# SMPS.net
KiCad netlist of a schematic drawn in Altium Designer
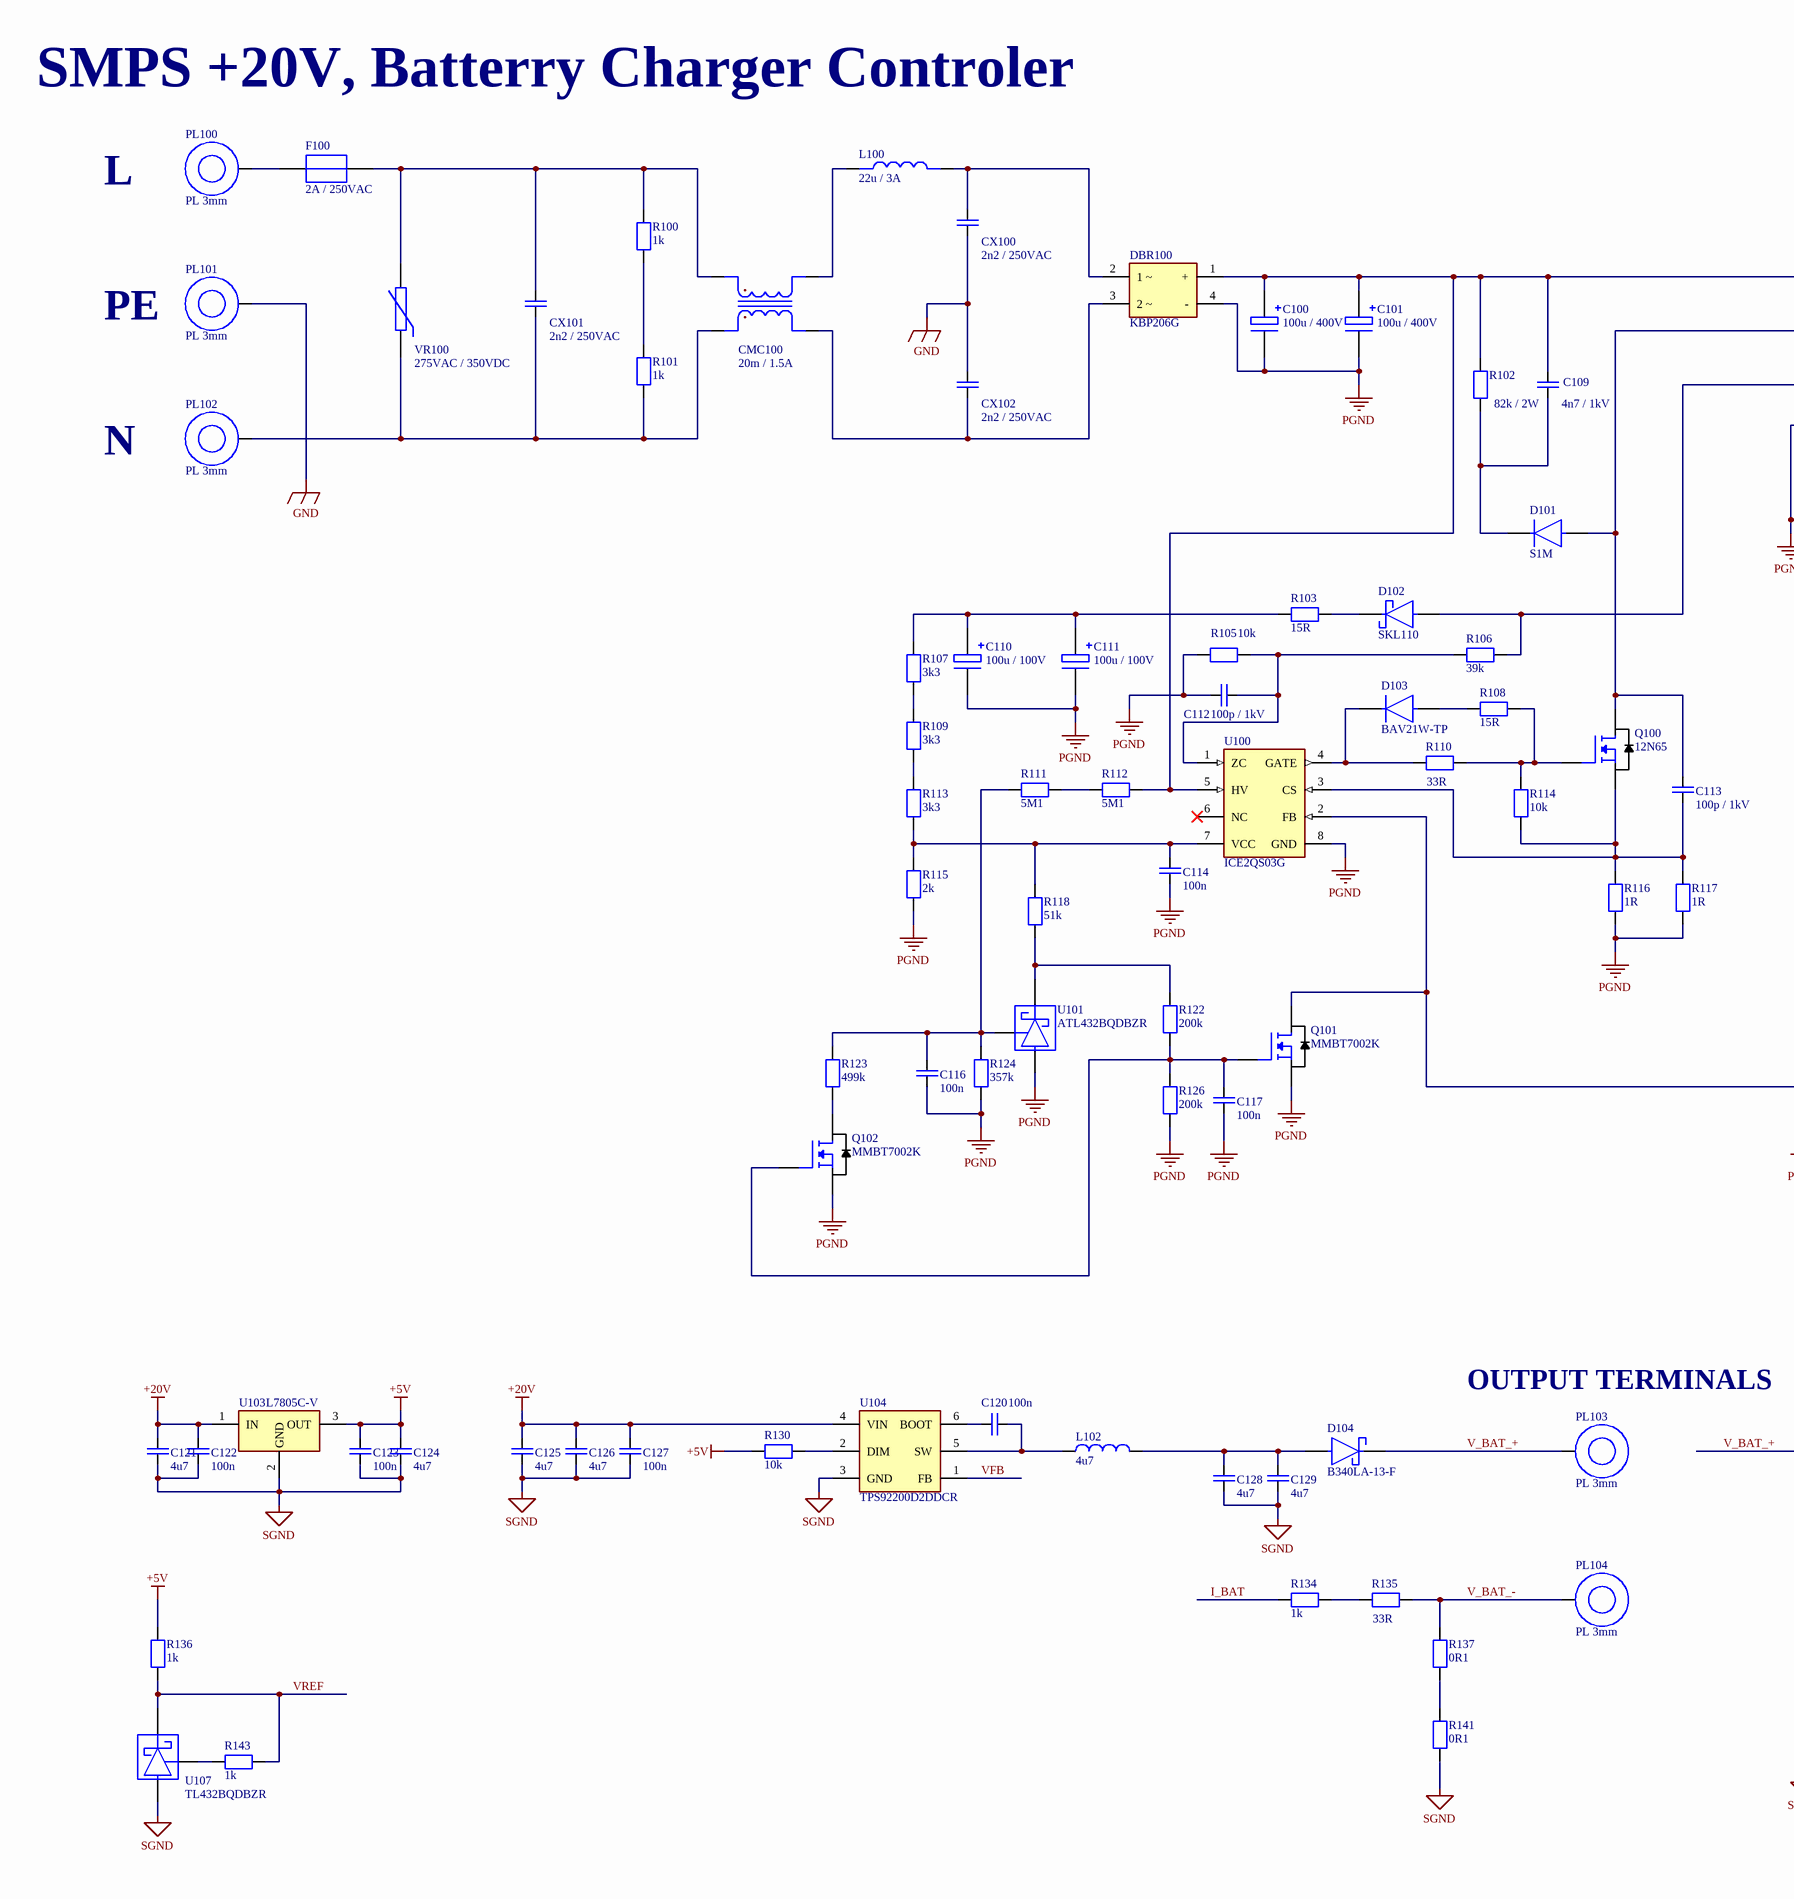
[diagram p0: SMPS.SchDoc, left]
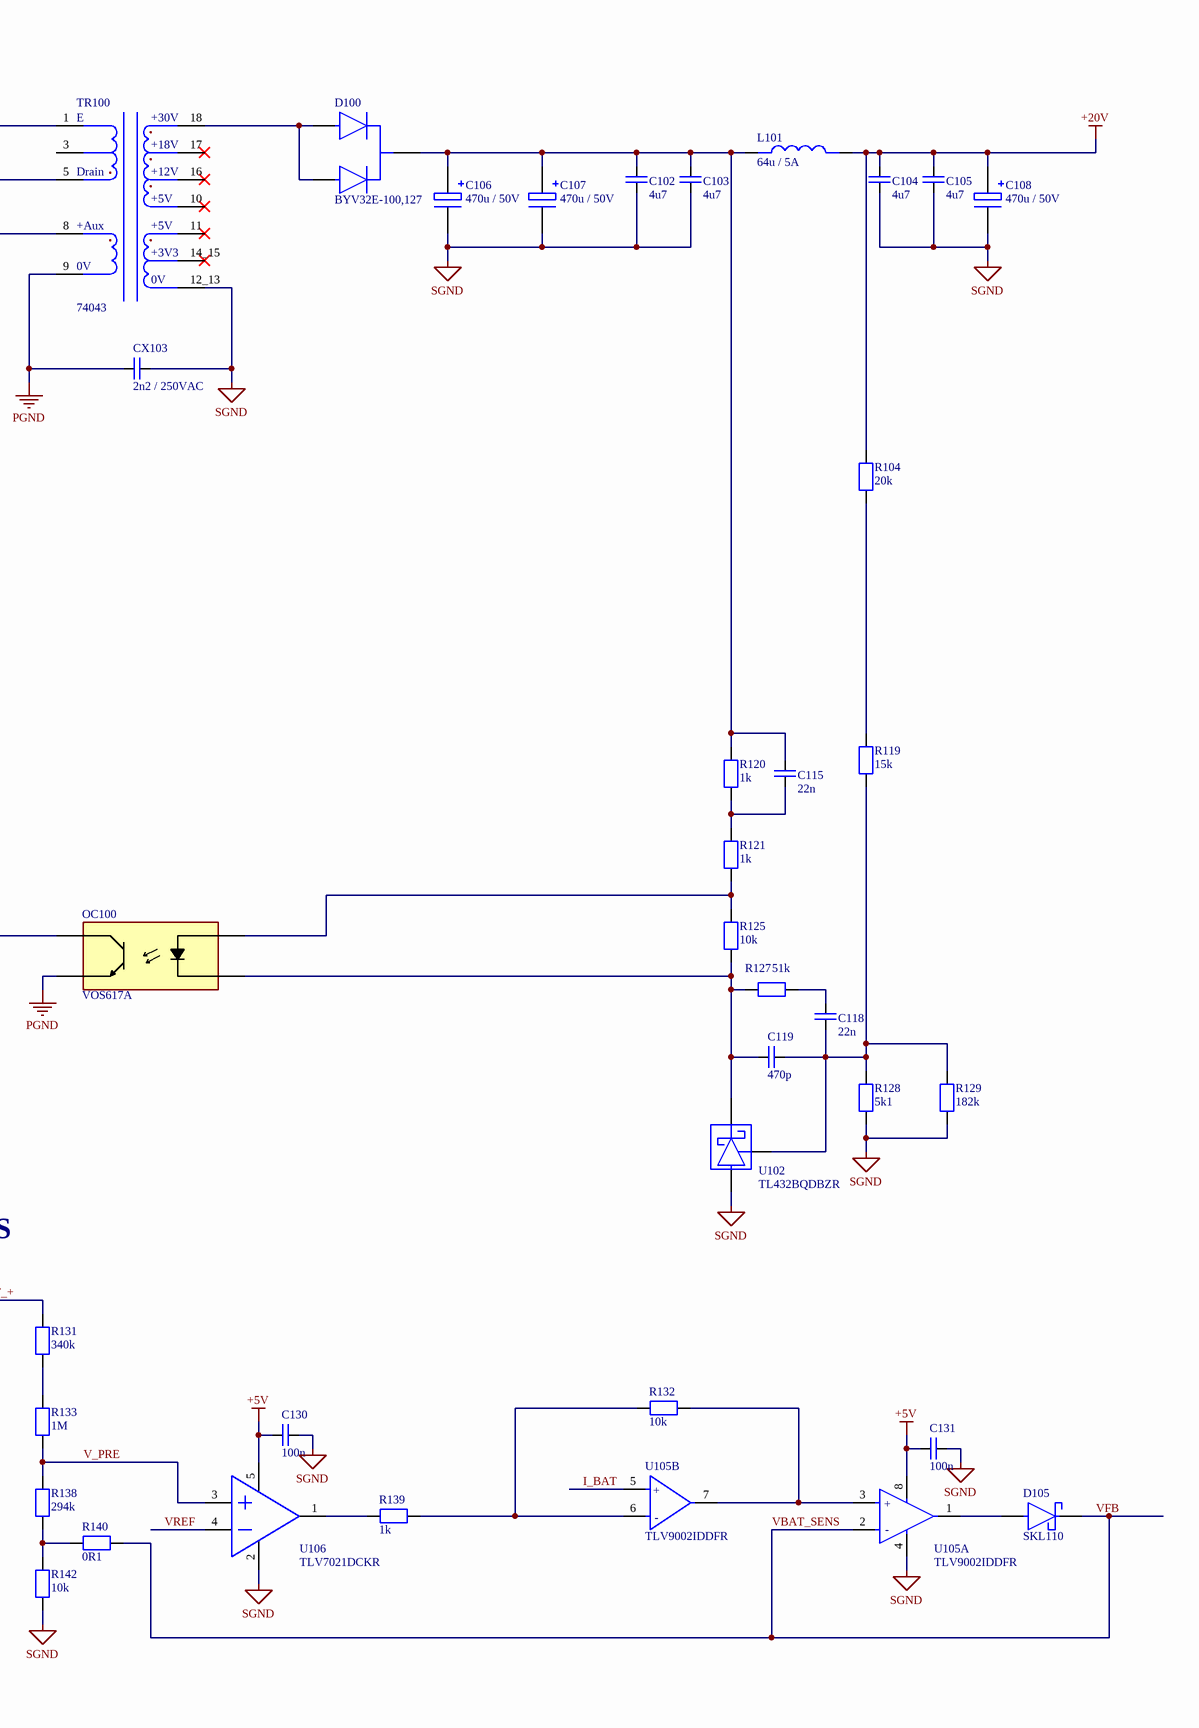
[diagram p1: SMPS.SchDoc, right]

(export (version "E")
  (design (tool "Eeschema 10.0.6"))
  (components
    (comp (ref "C100")
      (value "100u / 400V")
      (footprint "EL_CAP_16X7_5")
      (description "Cap Aluminum Lytic 100uF 400V 20% (16 X 35.5mm) Radial 7.5mm 850mA 12000h 105C Automotive Bulk")
      (fields
        (field (name "MANUFACTURER") "Nichicon")
        (field (name "MANUFACTURER PART NUMBER") "UCY2G101MHD")
      )
      (libsource (lib "ER_SCHEMATIC_LIBRARY") (part "UCY2G101MHD"))
    )
    (comp (ref "C101")
      (value "100u / 400V")
      (footprint "EL_CAP_16X7_5")
      (description "Cap Aluminum Lytic 100uF 400V 20% (16 X 35.5mm) Radial 7.5mm 850mA 12000h 105C Automotive Bulk")
      (fields
        (field (name "MANUFACTURER") "Nichicon")
        (field (name "MANUFACTURER PART NUMBER") "UCY2G101MHD")
      )
      (libsource (lib "ER_SCHEMATIC_LIBRARY") (part "UCY2G101MHD"))
    )
    (comp (ref "C102")
      (value "4u7")
      (footprint "C0805")
      (description "CAP CER 4.7UF 50V X5R 0805")
      (fields
        (field (name "MANUFACTURER") "Samsung")
        (field (name "MANUFACTURER PART NUMBER") "CL21A475KBQNNNE")
      )
      (libsource (lib "ER_SCHEMATIC_LIBRARY") (part "CL21A475KBQNNNE"))
    )
    (comp (ref "C103")
      (value "4u7")
      (footprint "C0805")
      (description "CAP CER 4.7UF 50V X5R 0805")
      (fields
        (field (name "MANUFACTURER") "Samsung")
        (field (name "MANUFACTURER PART NUMBER") "CL21A475KBQNNNE")
      )
      (libsource (lib "ER_SCHEMATIC_LIBRARY") (part "CL21A475KBQNNNE"))
    )
    (comp (ref "C104")
      (value "4u7")
      (footprint "C0805")
      (description "CAP CER 4.7UF 50V X5R 0805")
      (fields
        (field (name "MANUFACTURER") "Samsung")
        (field (name "MANUFACTURER PART NUMBER") "CL21A475KBQNNNE")
      )
      (libsource (lib "ER_SCHEMATIC_LIBRARY") (part "CL21A475KBQNNNE"))
    )
    (comp (ref "C105")
      (value "4u7")
      (footprint "C0805")
      (description "CAP CER 4.7UF 50V X5R 0805")
      (fields
        (field (name "MANUFACTURER") "Samsung")
        (field (name "MANUFACTURER PART NUMBER") "CL21A475KBQNNNE")
      )
      (libsource (lib "ER_SCHEMATIC_LIBRARY") (part "CL21A475KBQNNNE"))
    )
    (comp (ref "C106")
      (value "470u / 50V")
      (footprint "EL_CAP_12_5X5")
      (description "Kondensator: elektrolityczny; THT; 470uF; 50VDC; Ø12,5x20mm; ±20%")
      (fields (field (name "MANUFACTURER PART NUMBER") "PF1H471MNN1220"))
      (libsource (lib "ER_SCHEMATIC_LIBRARY") (part "PF1H471MNN1220"))
    )
    (comp (ref "C107")
      (value "470u / 50V")
      (footprint "EL_CAP_12_5X5")
      (description "Kondensator: elektrolityczny; THT; 470uF; 50VDC; Ø12,5x20mm; ±20%")
      (fields (field (name "MANUFACTURER PART NUMBER") "PF1H471MNN1220"))
      (libsource (lib "ER_SCHEMATIC_LIBRARY") (part "PF1H471MNN1220"))
    )
    (comp (ref "C108")
      (value "470u / 50V")
      (footprint "EL_CAP_12_5X5")
      (description "Kondensator: elektrolityczny; THT; 470uF; 50VDC; Ø12,5x20mm; ±20%")
      (fields (field (name "MANUFACTURER PART NUMBER") "PF1H471MNN1220"))
      (libsource (lib "ER_SCHEMATIC_LIBRARY") (part "PF1H471MNN1220"))
    )
    (comp (ref "C109")
      (value "4n7 / 1kV")
      (footprint "C1206")
      (fields
        (field (name "MANUFACTURER") "Multicomp")
        (field (name "MANUFACTURER PART NUMBER") "MC1206B472K102CT")
        (field (name "TOLERANCE") "10%")
      )
      (libsource (lib "ER_SCHEMATIC_LIBRARY") (part "MC1206B472K102CT"))
    )
    (comp (ref "C110")
      (value "100u / 100V")
      (footprint "EL_CAP_10X5")
      (description "Kondensator: elektrolityczny; THT; 100uF; 100VDC; Ø10x20mm; ±20%")
      (libsource (lib "ER_SCHEMATIC_LIBRARY") (part "EKM107M2AG20RRSHP"))
    )
    (comp (ref "C111")
      (value "100u / 100V")
      (footprint "EL_CAP_10X5")
      (description "Kondensator: elektrolityczny; THT; 100uF; 100VDC; Ø10x20mm; ±20%")
      (libsource (lib "ER_SCHEMATIC_LIBRARY") (part "EKM107M2AG20RRSHP"))
    )
    (comp (ref "C112")
      (value "100p / 1kV")
      (footprint "FILM_CAP_R5MM_4_5X6X7_2")
      (description "Kondensator: polipropylenowy; 100pF; 4,5x6x7,2mm; THT; ±5%; 5mm")
      (fields
        (field (name "MANUFACTURER") "WIMA")
        (field (name "MANUFACTURER PART NUMBER") "FKP2O101001D00JO00")
      )
      (libsource (lib "ER_SCHEMATIC_LIBRARY") (part "FKP2O101001D00JO00"))
    )
    (comp (ref "C113")
      (value "100p / 1kV")
      (footprint "FILM_CAP_R5MM_4_5X6X7_2")
      (description "Kondensator: polipropylenowy; 100pF; 4,5x6x7,2mm; THT; ±5%; 5mm")
      (fields
        (field (name "MANUFACTURER") "WIMA")
        (field (name "MANUFACTURER PART NUMBER") "FKP2O101001D00JO00")
      )
      (libsource (lib "ER_SCHEMATIC_LIBRARY") (part "FKP2O101001D00JO00"))
    )
    (comp (ref "C114")
      (value "100n")
      (footprint "C1206")
      (description "1206 0.1 uF 100 V ±10% Tolerance X7R SMT Multilayer Ceramic Capacitor")
      (fields
        (field (name "MANUFACTURER") "Yageo")
        (field (name "MANUFACTURER PART NUMBER") "CC1206KKX7R0BB104")
      )
      (libsource (lib "ER_SCHEMATIC_LIBRARY") (part "CC1206KKX7R0BB104"))
    )
    (comp (ref "C115")
      (value "22n")
      (footprint "C0603")
      (description "Cap Ceramic 0.022uF 50V X7R 10% SMD 0603 125C Paper T/R")
      (fields
        (field (name "MANUFACTURER") "Kyocera AVX")
        (field (name "MANUFACTURER PART NUMBER") "06035C223K4T2A")
      )
      (libsource (lib "ER_SCHEMATIC_LIBRARY") (part "06035C223K4T2A"))
    )
    (comp (ref "C116")
      (value "100n")
      (footprint "C1206")
      (description "1206 0.1 uF 100 V ±10% Tolerance X7R SMT Multilayer Ceramic Capacitor")
      (fields
        (field (name "MANUFACTURER") "Yageo")
        (field (name "MANUFACTURER PART NUMBER") "CC1206KKX7R0BB104")
      )
      (libsource (lib "ER_SCHEMATIC_LIBRARY") (part "CC1206KKX7R0BB104"))
    )
    (comp (ref "C117")
      (value "100n")
      (footprint "C1206")
      (description "1206 0.1 uF 100 V ±10% Tolerance X7R SMT Multilayer Ceramic Capacitor")
      (fields
        (field (name "MANUFACTURER") "Yageo")
        (field (name "MANUFACTURER PART NUMBER") "CC1206KKX7R0BB104")
      )
      (libsource (lib "ER_SCHEMATIC_LIBRARY") (part "CC1206KKX7R0BB104"))
    )
    (comp (ref "C118")
      (value "22n")
      (footprint "C0603")
      (description "Cap Ceramic 0.022uF 50V X7R 10% SMD 0603 125C Paper T/R")
      (fields
        (field (name "MANUFACTURER") "Kyocera AVX")
        (field (name "MANUFACTURER PART NUMBER") "06035C223K4T2A")
      )
      (libsource (lib "ER_SCHEMATIC_LIBRARY") (part "06035C223K4T2A"))
    )
    (comp (ref "C119")
      (value "470p")
      (footprint "C0603")
      (description "0603 470 pF 50 V ±5 % Tolerance C0G/NP0 SMT Multilayer Ceramic Capacitor")
      (fields
        (field (name "MANUFACTURER") "Kyocera AVX")
        (field (name "MANUFACTURER PART NUMBER") "06035A471JAT2A")
      )
      (libsource (lib "ER_SCHEMATIC_LIBRARY") (part "06035A471JAT2A"))
    )
    (comp (ref "C120")
      (value "100n")
      (footprint "C1206")
      (description "1206 0.1 uF 100 V ±10% Tolerance X7R SMT Multilayer Ceramic Capacitor")
      (fields
        (field (name "MANUFACTURER") "Yageo")
        (field (name "MANUFACTURER PART NUMBER") "CC1206KKX7R0BB104")
      )
      (libsource (lib "ER_SCHEMATIC_LIBRARY") (part "CC1206KKX7R0BB104"))
    )
    (comp (ref "C121")
      (value "4u7")
      (footprint "C0805")
      (description "CAP CER 4.7UF 50V X5R 0805")
      (fields
        (field (name "MANUFACTURER") "Samsung")
        (field (name "MANUFACTURER PART NUMBER") "CL21A475KBQNNNE")
      )
      (libsource (lib "ER_SCHEMATIC_LIBRARY") (part "CL21A475KBQNNNE"))
    )
    (comp (ref "C122")
      (value "100n")
      (footprint "C1206")
      (description "1206 0.1 uF 100 V ±10% Tolerance X7R SMT Multilayer Ceramic Capacitor")
      (fields
        (field (name "MANUFACTURER") "Yageo")
        (field (name "MANUFACTURER PART NUMBER") "CC1206KKX7R0BB104")
      )
      (libsource (lib "ER_SCHEMATIC_LIBRARY") (part "CC1206KKX7R0BB104"))
    )
    (comp (ref "C123")
      (value "100n")
      (footprint "C1206")
      (description "1206 0.1 uF 100 V ±10% Tolerance X7R SMT Multilayer Ceramic Capacitor")
      (fields
        (field (name "MANUFACTURER") "Yageo")
        (field (name "MANUFACTURER PART NUMBER") "CC1206KKX7R0BB104")
      )
      (libsource (lib "ER_SCHEMATIC_LIBRARY") (part "CC1206KKX7R0BB104"))
    )
    (comp (ref "C124")
      (value "4u7")
      (footprint "C0805")
      (description "CAP CER 4.7UF 50V X5R 0805")
      (fields
        (field (name "MANUFACTURER") "Samsung")
        (field (name "MANUFACTURER PART NUMBER") "CL21A475KBQNNNE")
      )
      (libsource (lib "ER_SCHEMATIC_LIBRARY") (part "CL21A475KBQNNNE"))
    )
    (comp (ref "C125")
      (value "4u7")
      (footprint "C0805")
      (description "CAP CER 4.7UF 50V X5R 0805")
      (fields
        (field (name "MANUFACTURER") "Samsung")
        (field (name "MANUFACTURER PART NUMBER") "CL21A475KBQNNNE")
      )
      (libsource (lib "ER_SCHEMATIC_LIBRARY") (part "CL21A475KBQNNNE"))
    )
    (comp (ref "C126")
      (value "4u7")
      (footprint "C0805")
      (description "CAP CER 4.7UF 50V X5R 0805")
      (fields
        (field (name "MANUFACTURER") "Samsung")
        (field (name "MANUFACTURER PART NUMBER") "CL21A475KBQNNNE")
      )
      (libsource (lib "ER_SCHEMATIC_LIBRARY") (part "CL21A475KBQNNNE"))
    )
    (comp (ref "C127")
      (value "100n")
      (footprint "C1206")
      (description "1206 0.1 uF 100 V ±10% Tolerance X7R SMT Multilayer Ceramic Capacitor")
      (fields
        (field (name "MANUFACTURER") "Yageo")
        (field (name "MANUFACTURER PART NUMBER") "CC1206KKX7R0BB104")
      )
      (libsource (lib "ER_SCHEMATIC_LIBRARY") (part "CC1206KKX7R0BB104"))
    )
    (comp (ref "C128")
      (value "4u7")
      (footprint "C0805")
      (description "CAP CER 4.7UF 50V X5R 0805")
      (fields
        (field (name "MANUFACTURER") "Samsung")
        (field (name "MANUFACTURER PART NUMBER") "CL21A475KBQNNNE")
      )
      (libsource (lib "ER_SCHEMATIC_LIBRARY") (part "CL21A475KBQNNNE"))
    )
    (comp (ref "C129")
      (value "4u7")
      (footprint "C0805")
      (description "CAP CER 4.7UF 50V X5R 0805")
      (fields
        (field (name "MANUFACTURER") "Samsung")
        (field (name "MANUFACTURER PART NUMBER") "CL21A475KBQNNNE")
      )
      (libsource (lib "ER_SCHEMATIC_LIBRARY") (part "CL21A475KBQNNNE"))
    )
    (comp (ref "C130")
      (value "100n")
      (footprint "C1206")
      (description "1206 0.1 uF 100 V ±10% Tolerance X7R SMT Multilayer Ceramic Capacitor")
      (fields
        (field (name "MANUFACTURER") "Yageo")
        (field (name "MANUFACTURER PART NUMBER") "CC1206KKX7R0BB104")
      )
      (libsource (lib "ER_SCHEMATIC_LIBRARY") (part "CC1206KKX7R0BB104"))
    )
    (comp (ref "C131")
      (value "100n")
      (footprint "C1206")
      (description "1206 0.1 uF 100 V ±10% Tolerance X7R SMT Multilayer Ceramic Capacitor")
      (fields
        (field (name "MANUFACTURER") "Yageo")
        (field (name "MANUFACTURER PART NUMBER") "CC1206KKX7R0BB104")
      )
      (libsource (lib "ER_SCHEMATIC_LIBRARY") (part "CC1206KKX7R0BB104"))
    )
    (comp (ref "CMC100")
      (value "20m / 1.5A")
      (footprint "EV28CMC")
      (description "Suppression Choke, Common Mode, 1.5 A , DCR Thru-Hole, Pin, EV/EH Series")
      (fields
        (field (name "MANUFACTURER") "Schaffner")
        (field (name "MANUFACTURER PART NUMBER") "EV28-1.5-02-20M")
      )
      (libsource (lib "ER_SCHEMATIC_LIBRARY") (part "EV28-1.5-02-20M"))
    )
    (comp (ref "CX100")
      (value "2n2 / 250VAC")
      (footprint "CX_THT_CAP_R_7_5_FI8")
      (description "Cap Ceramic Suppression X1/Y2 0.0022uF 250VAC E 20% (8 X 5mm) Radial 7.5mm 125 Bulk")
      (fields
        (field (name "MANUFACTURER") "Murata")
        (field (name "MANUFACTURER PART NUMBER") "DE2E3KY222MA3BM02F")
      )
      (libsource (lib "ER_SCHEMATIC_LIBRARY") (part "DE2E3KY222MA3BM02F"))
    )
    (comp (ref "CX101")
      (value "2n2 / 250VAC")
      (footprint "CX_THT_CAP_R_7_5_FI8")
      (description "Cap Ceramic Suppression X1/Y2 0.0022uF 250VAC E 20% (8 X 5mm) Radial 7.5mm 125 Bulk")
      (fields
        (field (name "MANUFACTURER") "Murata")
        (field (name "MANUFACTURER PART NUMBER") "DE2E3KY222MA3BM02F")
      )
      (libsource (lib "ER_SCHEMATIC_LIBRARY") (part "DE2E3KY222MA3BM02F"))
    )
    (comp (ref "CX102")
      (value "2n2 / 250VAC")
      (footprint "CX_THT_CAP_R_7_5_FI8")
      (description "Cap Ceramic Suppression X1/Y2 0.0022uF 250VAC E 20% (8 X 5mm) Radial 7.5mm 125 Bulk")
      (fields
        (field (name "MANUFACTURER") "Murata")
        (field (name "MANUFACTURER PART NUMBER") "DE2E3KY222MA3BM02F")
      )
      (libsource (lib "ER_SCHEMATIC_LIBRARY") (part "DE2E3KY222MA3BM02F"))
    )
    (comp (ref "CX103")
      (value "2n2 / 250VAC")
      (footprint "CX_THT_CAP_R_7_5_FI8")
      (description "Cap Ceramic Suppression X1/Y2 0.0022uF 250VAC E 20% (8 X 5mm) Radial 7.5mm 125 Bulk")
      (fields
        (field (name "MANUFACTURER") "Murata")
        (field (name "MANUFACTURER PART NUMBER") "DE2E3KY222MA3BM02F")
      )
      (libsource (lib "ER_SCHEMATIC_LIBRARY") (part "DE2E3KY222MA3BM02F"))
    )
    (comp (ref "D100")
      (value "BYV32E-100,127")
      (footprint "TO220AB")
      (description "Diode Switching 100V 20A 3-Pin(3+Tab) TO-220AB Tube")
      (fields (field (name "MANUFACTURER") "NXP Semiconductors"))
      (libsource (lib "ER_SCHEMATIC_LIBRARY") (part "BYV32E-100,127"))
    )
    (comp (ref "D101")
      (value "S1M")
      (footprint "SMA")
      (description "VR=1000V IF=1A 6.6pF Trr=1.8us P=1.4W")
      (fields (field (name "MANUFACTURER") "ON Semiconductor / Fairchild") (field (name "VOLTAGE") "1kV"))
      (libsource (lib "ER_SCHEMATIC_LIBRARY") (part "S1M"))
    )
    (comp (ref "D102")
      (value "SKL110")
      (footprint "SOD123FL")
      (description "Schottky Diode, SOD-123FL, 100V, 1.00A")
      (fields (field (name "MANUFACTURER") "Diotec"))
      (libsource (lib "ER_SCHEMATIC_LIBRARY") (part "SKL110"))
    )
    (comp (ref "D103")
      (value "BAV21W-TP")
      (footprint "SOD123FL")
      (description "Rectifier Diode Small Signal Switching 250V 0.25A 50ns 2-Pin SOD-123 T/R")
      (fields (field (name "MANUFACTURER") "MCC") (field (name "VOLTAGE") "250V"))
      (libsource (lib "ER_SCHEMATIC_LIBRARY") (part "BAV21W-TP"))
    )
    (comp (ref "D104")
      (value "B340LA-13-F")
      (footprint "SMA")
      (description "VR=40V IF=3A 200pF")
      (fields (field (name "MANUFACTURER") "Diodes"))
      (libsource (lib "ER_SCHEMATIC_LIBRARY") (part "B340LA-13-F"))
    )
    (comp (ref "D105")
      (value "SKL110")
      (footprint "SOD123FL")
      (description "Schottky Diode, SOD-123FL, 100V, 1.00A")
      (fields (field (name "MANUFACTURER") "Diotec"))
      (libsource (lib "ER_SCHEMATIC_LIBRARY") (part "SKL110"))
    )
    (comp (ref "DBR100")
      (value "KBP206G")
      (footprint "FP-KBP-MFG")
      (description "Rectifier Bridge Diode Single 600V 2A 4-Pin Case KBP Tube / RECT BRIDGE GPP 600V 2A KBP")
      (fields (field (name "MANUFACTURER") "Diodes"))
      (libsource (lib "ER_SCHEMATIC_LIBRARY") (part "KBP206G"))
    )
    (comp (ref "F100")
      (value "2A / 250VAC")
      (footprint "FUSE_SMD_5X20")
      (description "Fuse Miniature Slow Blow Acting 2A 250V Holder Cartridge 5 X 20mm Ceramic Bag CCC/VDE/cULus")
      (fields
        (field (name "MANUFACTURER") "Schurter")
        (field (name "MANUFACTURER PART NUMBER") "0001.2707.11")
      )
      (libsource (lib "ER_SCHEMATIC_LIBRARY") (part "0001.2707.11"))
    )
    (comp (ref "L100")
      (value "22u / 3A")
      (footprint "POWER_INDUCTOR_THT_8X14")
      (description "Fixed Ind 22UH 3A 50 Mohm Th")
      (fields (field (name "MANUFACTURER") "Nuvotem") (field (name "MANUFACTURER PART NUMBER") "DPO-3.0-22"))
      (libsource (lib "ER_SCHEMATIC_LIBRARY") (part "DPO-3.0-22"))
    )
    (comp (ref "L101")
      (value "64u / 5A")
      (footprint "POWER_INDUCTOR_THT_16X27")
      (description "Dławik: drutowy; THT; 64uH; 5A; 60mΩ")
      (fields (field (name "MANUFACTURER PART NUMBER") "DLV-640-M5.0"))
      (libsource (lib "ER_SCHEMATIC_LIBRARY") (part "DLV-640-M5.0"))
    )
    (comp (ref "L102")
      (value "4u7")
      (footprint "WE-TPC-1028-XL")
      (description "Power Choke Shielded Wirewound 4.7uH 30% 100KHz Ferrite 4.6A 23mOhm DCR T/R")
      (fields
        (field (name "MANUFACTURER") "Wurth Electronics")
        (field (name "MANUFACTURER PART NUMBER") "7440650047")
      )
      (libsource (lib "ER_SCHEMATIC_LIBRARY") (part "7440650047"))
    )
    (comp (ref "OC100")
      (value "VOS617A")
      (footprint "OC_SOP_4")
      (description "Optocoupler DC-IN 1-CH Transistor DC-OUT 4-Pin SSOP T/R")
      (fields
        (field (name "MANUFACTURER") "Vishay Semiconductors")
        (field (name "MANUFACTURER PART NUMBER") "VOS617A-X001T")
      )
      (libsource (lib "ER_SCHEMATIC_LIBRARY") (part "VOS617A-X001T"))
    )
    (comp (ref "PL100")
      (value "PL 3mm")
      (footprint "PL3MM")
      (description "Pole lutownicze 3mm")
      (libsource (lib "ER_SCHEMATIC_LIBRARY") (part "Pole lutownicze 3mm"))
    )
    (comp (ref "PL101")
      (value "PL 3mm")
      (footprint "PL3MM")
      (description "Pole lutownicze 3mm")
      (libsource (lib "ER_SCHEMATIC_LIBRARY") (part "Pole lutownicze 3mm"))
    )
    (comp (ref "PL102")
      (value "PL 3mm")
      (footprint "PL3MM")
      (description "Pole lutownicze 3mm")
      (libsource (lib "ER_SCHEMATIC_LIBRARY") (part "Pole lutownicze 3mm"))
    )
    (comp (ref "PL103")
      (value "PL 3mm")
      (footprint "PL3MM")
      (description "Pole lutownicze 3mm")
      (libsource (lib "ER_SCHEMATIC_LIBRARY") (part "Pole lutownicze 3mm"))
    )
    (comp (ref "PL104")
      (value "PL 3mm")
      (footprint "PL3MM")
      (description "Pole lutownicze 3mm")
      (libsource (lib "ER_SCHEMATIC_LIBRARY") (part "Pole lutownicze 3mm"))
    )
    (comp (ref "Q100")
      (value "12N65")
      (footprint "TO220F")
      (description "Tranzystor: N-MOSFET; unipolarny; 650V; 12A; 33,2W; TO220F")
      (libsource (lib "ER_SCHEMATIC_LIBRARY") (part "12N65"))
    )
    (comp (ref "Q101")
      (value "MMBT7002K")
      (footprint "SOT23")
      (description "MOSFETs (Field Effect Transistor), SOT-23, 60V, 0.3A, N, 0.350W")
      (fields (field (name "MANUFACTURER") "Diotec"))
      (libsource (lib "ER_SCHEMATIC_LIBRARY") (part "MMBT7002K"))
    )
    (comp (ref "Q102")
      (value "MMBT7002K")
      (footprint "SOT23")
      (description "MOSFETs (Field Effect Transistor), SOT-23, 60V, 0.3A, N, 0.350W")
      (fields (field (name "MANUFACTURER") "Diotec"))
      (libsource (lib "ER_SCHEMATIC_LIBRARY") (part "MMBT7002K"))
    )
    (comp (ref "R100")
      (value "1k")
      (footprint "R1206")
      (description "Res Thick Film 1206 1.2K Ohm 5% 1/4W ±100ppm/°C Molded SMD SMD Paper T/R")
      (fields
        (field (name "MANUFACTURER") "Yageo")
        (field (name "MANUFACTURER PART NUMBER") "RC1206JR-071K2L")
      )
      (libsource (lib "ER_SCHEMATIC_LIBRARY") (part "RC1206JR-071K2L"))
    )
    (comp (ref "R101")
      (value "1k")
      (footprint "R1206")
      (description "Res Thick Film 1206 1.2K Ohm 5% 1/4W ±100ppm/°C Molded SMD SMD Paper T/R")
      (fields
        (field (name "MANUFACTURER") "Yageo")
        (field (name "MANUFACTURER PART NUMBER") "RC1206JR-071K2L")
      )
      (libsource (lib "ER_SCHEMATIC_LIBRARY") (part "RC1206JR-071K2L"))
    )
    (comp (ref "R102")
      (value "82k / 2W")
      (footprint "RAxialFi4")
      (description "Rezystor: power metal; THT; 82kΩ; 2W; ±5%; Ø4x11mm; 350ppm/°C")
      (fields (field (name "MANUFACTURER PART NUMBER") "PMR02SJ0823A10"))
      (libsource (lib "ER_SCHEMATIC_LIBRARY") (part "PMR2S-82K"))
    )
    (comp (ref "R103")
      (value "15R")
      (footprint "R1206")
      (description "Resistor: thick film; SMD; 1206; 15O; 0.25W; ±5%; -55÷125°C")
      (fields
        (field (name "MANUFACTURER") "Royal Electronic Factory")
        (field (name "MANUFACTURER PART NUMBER") "1206S4J0150T5E")
      )
      (libsource (lib "ER_SCHEMATIC_LIBRARY") (part "1206S4J0150T5E"))
    )
    (comp (ref "R104")
      (value "20k")
      (footprint "R0603")
      (description "Res Thick Film 0603 20K Ohm 1% 0.1W(1/10W) ±100ppm/C Pad SMD T/R")
      (fields
        (field (name "MANUFACTURER") "Walsin Technologies")
        (field (name "MANUFACTURER PART NUMBER") "WR06X2002FTL")
      )
      (libsource (lib "ER_SCHEMATIC_LIBRARY") (part "WR06X2002FTL"))
    )
    (comp (ref "R105")
      (value "10k")
      (footprint "R1206")
      (description "Res Thick Film 1206 10K Ohm 5% 0.25W(1/4W) ±100ppm/°C Pad SMD T/R")
      (fields
        (field (name "MANUFACTURER") "Royal Electronic Factory")
        (field (name "MANUFACTURER PART NUMBER") "1206S4J0103T5E")
      )
      (libsource (lib "ER_SCHEMATIC_LIBRARY") (part "1206S4J0103T5E"))
    )
    (comp (ref "R106")
      (value "39k")
      (footprint "R1206")
      (description "Rezystor: thick film; SMD; 1206; 39kΩ; 0,25W; ±5%; -55÷125°C")
      (fields
        (field (name "MANUFACTURER") "Royal Electronic Factory")
        (field (name "MANUFACTURER PART NUMBER") "1206S4J0393T5E")
      )
      (libsource (lib "ER_SCHEMATIC_LIBRARY") (part "1206S4J0393T5E"))
    )
    (comp (ref "R107")
      (value "3k3")
      (footprint "R1206")
      (description "Cermet resistor 3.3 kΩ SMD 1206 0.25 W 5 % 100 ±ppm/°C Royalohm 1206S4J0332T5E 1 pc(s)")
      (fields
        (field (name "MANUFACTURER") "Royal Electronic Factory")
        (field (name "MANUFACTURER PART NUMBER") "1206S4J0332T5E")
      )
      (libsource (lib "ER_SCHEMATIC_LIBRARY") (part "1206S4J0332T5E"))
    )
    (comp (ref "R108")
      (value "15R")
      (footprint "R1206")
      (description "Resistor: thick film; SMD; 1206; 15O; 0.25W; ±5%; -55÷125°C")
      (fields
        (field (name "MANUFACTURER") "Royal Electronic Factory")
        (field (name "MANUFACTURER PART NUMBER") "1206S4J0150T5E")
      )
      (libsource (lib "ER_SCHEMATIC_LIBRARY") (part "1206S4J0150T5E"))
    )
    (comp (ref "R109")
      (value "3k3")
      (footprint "R1206")
      (description "Cermet resistor 3.3 kΩ SMD 1206 0.25 W 5 % 100 ±ppm/°C Royalohm 1206S4J0332T5E 1 pc(s)")
      (fields
        (field (name "MANUFACTURER") "Royal Electronic Factory")
        (field (name "MANUFACTURER PART NUMBER") "1206S4J0332T5E")
      )
      (libsource (lib "ER_SCHEMATIC_LIBRARY") (part "1206S4J0332T5E"))
    )
    (comp (ref "R110")
      (value "33R")
      (footprint "R1206")
      (description "Rezystor: thick film; SMD; 1206; 33Ω; 0,25W; ±5%; -55÷125°C")
      (fields
        (field (name "MANUFACTURER") "Royal Electronic Factory")
        (field (name "MANUFACTURER PART NUMBER") "1206S4J0330T5E")
      )
      (libsource (lib "ER_SCHEMATIC_LIBRARY") (part "1206S4J0330T5E"))
    )
    (comp (ref "R111")
      (value "5M1")
      (footprint "R1206")
      (description "Rezystor: thick film; SMD; 1206; 5,1MΩ; 0,25W; ±1%; -55÷125°C")
      (fields
        (field (name "MANUFACTURER") "Royal Electronic Factory")
        (field (name "MANUFACTURER PART NUMBER") "1206S4F5104T5E")
      )
      (libsource (lib "ER_SCHEMATIC_LIBRARY") (part "1206S4F5104T5E"))
    )
    (comp (ref "R112")
      (value "5M1")
      (footprint "R1206")
      (description "Rezystor: thick film; SMD; 1206; 5,1MΩ; 0,25W; ±1%; -55÷125°C")
      (fields
        (field (name "MANUFACTURER") "Royal Electronic Factory")
        (field (name "MANUFACTURER PART NUMBER") "1206S4F5104T5E")
      )
      (libsource (lib "ER_SCHEMATIC_LIBRARY") (part "1206S4F5104T5E"))
    )
    (comp (ref "R113")
      (value "3k3")
      (footprint "R1206")
      (description "Cermet resistor 3.3 kΩ SMD 1206 0.25 W 5 % 100 ±ppm/°C Royalohm 1206S4J0332T5E 1 pc(s)")
      (fields
        (field (name "MANUFACTURER") "Royal Electronic Factory")
        (field (name "MANUFACTURER PART NUMBER") "1206S4J0332T5E")
      )
      (libsource (lib "ER_SCHEMATIC_LIBRARY") (part "1206S4J0332T5E"))
    )
    (comp (ref "R114")
      (value "10k")
      (footprint "R0603")
      (description "Rezystor: thick film; SMD; 0603; 10kΩ; 0,125W; ±5%; -55÷155°C")
      (fields (field (name "MANUFACTURER PART NUMBER") "WF06P103JTL"))
      (libsource (lib "ER_SCHEMATIC_LIBRARY") (part "WF06P103JTL"))
    )
    (comp (ref "R115")
      (value "2k")
      (footprint "R1206")
      (description "Rezystor: thick film; SMD; 1206; 2kΩ; 0,25W; ±5%; -55÷125°C")
      (fields
        (field (name "MANUFACTURER") "Royal Electronic Factory")
        (field (name "MANUFACTURER PART NUMBER") "1206S4J0202T5E")
      )
      (libsource (lib "ER_SCHEMATIC_LIBRARY") (part "1206S4J0202T5E"))
    )
    (comp (ref "R116")
      (value "1R")
      (footprint "R1206")
      (description "Rezystor: thick film; SMD; 1206; 1Ω; 0,25W; ±5%; -55÷125°C")
      (fields
        (field (name "MANUFACTURER") "Royal Electronic Factory")
        (field (name "MANUFACTURER PART NUMBER") "1206S4J010JT5E")
      )
      (libsource (lib "ER_SCHEMATIC_LIBRARY") (part "1206S4J010JT5E"))
    )
    (comp (ref "R117")
      (value "1R")
      (footprint "R1206")
      (description "Rezystor: thick film; SMD; 1206; 1Ω; 0,25W; ±5%; -55÷125°C")
      (fields
        (field (name "MANUFACTURER") "Royal Electronic Factory")
        (field (name "MANUFACTURER PART NUMBER") "1206S4J010JT5E")
      )
      (libsource (lib "ER_SCHEMATIC_LIBRARY") (part "1206S4J010JT5E"))
    )
    (comp (ref "R118")
      (value "51k")
      (footprint "R0603")
      (description "Rezystor: thick film; SMD; 0603; 51kΩ; 0,1W; ±5%; -55÷155°C")
      (fields
        (field (name "MANUFACTURER") "Royal Electronic Factory")
        (field (name "MANUFACTURER PART NUMBER") "0603SAJ0513T5E")
      )
      (libsource (lib "ER_SCHEMATIC_LIBRARY") (part "0603SAJ0513T5E"))
    )
    (comp (ref "R119")
      (value "15k")
      (footprint "R0603")
      (description "0603 15000±5% SMD Resistor")
      (fields
        (field (name "MANUFACTURER") "Royal Electronic Factory")
        (field (name "MANUFACTURER PART NUMBER") "0603SAJ0153T5E")
      )
      (libsource (lib "ER_SCHEMATIC_LIBRARY") (part "0603SAJ0153T5E"))
    )
    (comp (ref "R120")
      (value "1k")
      (footprint "R0603")
      (description "Rezystor: thick film; SMD; 0603; 1kΩ; 0,125W; ±5%; -55÷155°C")
      (fields (field (name "MANUFACTURER PART NUMBER") "WF06P102JTL"))
      (libsource (lib "ER_SCHEMATIC_LIBRARY") (part "WF06P102JTL"))
    )
    (comp (ref "R121")
      (value "1k")
      (footprint "R0603")
      (description "Rezystor: thick film; SMD; 0603; 1kΩ; 0,125W; ±5%; -55÷155°C")
      (fields (field (name "MANUFACTURER PART NUMBER") "WF06P102JTL"))
      (libsource (lib "ER_SCHEMATIC_LIBRARY") (part "WF06P102JTL"))
    )
    (comp (ref "R122")
      (value "200k")
      (footprint "R0603")
      (description "Rezystor: thick film; SMD; 0603; 200kΩ; 0,1W; ±5%; -55÷155°C")
      (fields
        (field (name "MANUFACTURER") "Royal Electronic Factory")
        (field (name "MANUFACTURER PART NUMBER") "0603SAJ0204T5E")
      )
      (libsource (lib "ER_SCHEMATIC_LIBRARY") (part "0603SAJ0204T5E"))
    )
    (comp (ref "R123")
      (value "499k")
      (footprint "R0603")
      (description "MULTICOMP   MC0603SAF4993T5E   THICK FILM RESISTOR, 499KOHM, 100mW, 1%")
      (fields
        (field (name "MANUFACTURER") "Multicomp")
        (field (name "MANUFACTURER PART NUMBER") "MC0603SAF4993T5E")
      )
      (libsource (lib "ER_SCHEMATIC_LIBRARY") (part "MC0603SAF4993T5E"))
    )
    (comp (ref "R124")
      (value "357k")
      (footprint "R0603")
      (description "Res Thick Film 0603 357K Ohm 1% 1/10W ±100ppm/°C Molded SMD Punched Carrier T/R")
      (fields
        (field (name "MANUFACTURER") "Panasonic")
        (field (name "MANUFACTURER PART NUMBER") "ERJ-3EKF3573V")
      )
      (libsource (lib "ER_SCHEMATIC_LIBRARY") (part "ERJ-3EKF3573V"))
    )
    (comp (ref "R125")
      (value "10k")
      (footprint "R0603")
      (description "Rezystor: thick film; SMD; 0603; 10kΩ; 0,125W; ±5%; -55÷155°C")
      (fields (field (name "MANUFACTURER PART NUMBER") "WF06P103JTL"))
      (libsource (lib "ER_SCHEMATIC_LIBRARY") (part "WF06P103JTL"))
    )
    (comp (ref "R126")
      (value "200k")
      (footprint "R0603")
      (description "Rezystor: thick film; SMD; 0603; 200kΩ; 0,1W; ±5%; -55÷155°C")
      (fields
        (field (name "MANUFACTURER") "Royal Electronic Factory")
        (field (name "MANUFACTURER PART NUMBER") "0603SAJ0204T5E")
      )
      (libsource (lib "ER_SCHEMATIC_LIBRARY") (part "0603SAJ0204T5E"))
    )
    (comp (ref "R127")
      (value "51k")
      (footprint "R0603")
      (description "Rezystor: thick film; SMD; 0603; 51kΩ; 0,1W; ±5%; -55÷155°C")
      (fields
        (field (name "MANUFACTURER") "Royal Electronic Factory")
        (field (name "MANUFACTURER PART NUMBER") "0603SAJ0513T5E")
      )
      (libsource (lib "ER_SCHEMATIC_LIBRARY") (part "0603SAJ0513T5E"))
    )
    (comp (ref "R128")
      (value "5k1")
      (footprint "R0603")
      (description "0603 5100±5% SMD Resistor")
      (fields
        (field (name "MANUFACTURER") "Royal Electronic Factory")
        (field (name "MANUFACTURER PART NUMBER") "0603SAJ0512T5E")
      )
      (libsource (lib "ER_SCHEMATIC_LIBRARY") (part "0603SAJ0512T5E"))
    )
    (comp (ref "R129")
      (value "182k")
      (footprint "R0603")
      (description "Rezystor: thick film; SMD; 0603; 182kΩ; 0,1W; ±1%; -55÷155°C")
      (fields
        (field (name "MANUFACTURER") "Royal Ohm")
        (field (name "MANUFACTURER PART NUMBER") "0603SAF1823T5E")
      )
      (libsource (lib "ER_SCHEMATIC_LIBRARY") (part "0603SAF1823T5E"))
    )
    (comp (ref "R130")
      (value "10k")
      (footprint "R0603")
      (description "Rezystor: thick film; SMD; 0603; 10kΩ; 0,125W; ±5%; -55÷155°C")
      (fields (field (name "MANUFACTURER PART NUMBER") "WF06P103JTL"))
      (libsource (lib "ER_SCHEMATIC_LIBRARY") (part "WF06P103JTL"))
    )
    (comp (ref "R131")
      (value "340k")
      (footprint "R0805")
      (description "Res Thick Film 0805 340K Ohm 1% 0.125W(1/8W) ±100ppm/C Pad SMD T/R")
      (fields
        (field (name "MANUFACTURER") "Yageo")
        (field (name "MANUFACTURER PART NUMBER") "RC0805FR-07340KL")
      )
      (libsource (lib "ER_SCHEMATIC_LIBRARY") (part "RC0805FR-07340KL"))
    )
    (comp (ref "R132")
      (value "10k")
      (footprint "R0603")
      (description "Rezystor: thick film; SMD; 0603; 10kΩ; 0,125W; ±5%; -55÷155°C")
      (fields (field (name "MANUFACTURER PART NUMBER") "WF06P103JTL"))
      (libsource (lib "ER_SCHEMATIC_LIBRARY") (part "WF06P103JTL"))
    )
    (comp (ref "R133")
      (value "1M")
      (footprint "R0805")
      (description "Rezystor: thick film; SMD; 0805; 1MΩ; 0,125W; ±5%; -55÷125°C")
      (fields
        (field (name "MANUFACTURER") "Royal Electronic Factory")
        (field (name "MANUFACTURER PART NUMBER") "0805S8J0105T5E")
      )
      (libsource (lib "ER_SCHEMATIC_LIBRARY") (part "0805S8J0105T5E"))
    )
    (comp (ref "R134")
      (value "1k")
      (footprint "R0603")
      (description "Rezystor: thick film; SMD; 0603; 1kΩ; 0,125W; ±5%; -55÷155°C")
      (fields (field (name "MANUFACTURER PART NUMBER") "WF06P102JTL"))
      (libsource (lib "ER_SCHEMATIC_LIBRARY") (part "WF06P102JTL"))
    )
    (comp (ref "R135")
      (value "33R")
      (footprint "R1206")
      (description "Rezystor: thick film; SMD; 1206; 33Ω; 0,25W; ±5%; -55÷125°C")
      (fields
        (field (name "MANUFACTURER") "Royal Electronic Factory")
        (field (name "MANUFACTURER PART NUMBER") "1206S4J0330T5E")
      )
      (libsource (lib "ER_SCHEMATIC_LIBRARY") (part "1206S4J0330T5E"))
    )
    (comp (ref "R136")
      (value "1k")
      (footprint "R0603")
      (description "Rezystor: thick film; SMD; 0603; 1kΩ; 0,125W; ±5%; -55÷155°C")
      (fields (field (name "MANUFACTURER PART NUMBER") "WF06P102JTL"))
      (libsource (lib "ER_SCHEMATIC_LIBRARY") (part "WF06P102JTL"))
    )
    (comp (ref "R137")
      (value "0R1")
      (footprint "R1206")
      (description "Rezystor: thick film; pomiarowy; SMD; 1206; 100mΩ; 0,5W; ±5%")
      (fields
        (field (name "MANUFACTURER") "Viking Tech")
        (field (name "MANUFACTURER PART NUMBER") "CS06JTFUR100")
      )
      (libsource (lib "ER_SCHEMATIC_LIBRARY") (part "CS06JTFUR100"))
    )
    (comp (ref "R138")
      (value "294k")
      (footprint "R0805")
      (description "Res Thin Film 0805 294K Ohm 0.1% 1/8W ±25ppm/°C Molded SMD SMD Punched Carrier T/R")
      (fields
        (field (name "MANUFACTURER") "Panasonic")
        (field (name "MANUFACTURER PART NUMBER") "ERA-6AEB2943V")
      )
      (libsource (lib "ER_SCHEMATIC_LIBRARY") (part "ERA-6AEB2943V"))
    )
    (comp (ref "R139")
      (value "1k")
      (footprint "R0603")
      (description "Rezystor: thick film; SMD; 0603; 1kΩ; 0,125W; ±5%; -55÷155°C")
      (fields (field (name "MANUFACTURER PART NUMBER") "WF06P102JTL"))
      (libsource (lib "ER_SCHEMATIC_LIBRARY") (part "WF06P102JTL"))
    )
    (comp (ref "R140")
      (value "0R1")
      (footprint "R1206")
      (description "Rezystor: thick film; pomiarowy; SMD; 1206; 100mΩ; 0,5W; ±5%")
      (fields
        (field (name "MANUFACTURER") "Viking Tech")
        (field (name "MANUFACTURER PART NUMBER") "CS06JTFUR100")
      )
      (libsource (lib "ER_SCHEMATIC_LIBRARY") (part "CS06JTFUR100"))
    )
    (comp (ref "R141")
      (value "0R1")
      (footprint "R1206")
      (description "Rezystor: thick film; pomiarowy; SMD; 1206; 100mΩ; 0,5W; ±5%")
      (fields
        (field (name "MANUFACTURER") "Viking Tech")
        (field (name "MANUFACTURER PART NUMBER") "CS06JTFUR100")
      )
      (libsource (lib "ER_SCHEMATIC_LIBRARY") (part "CS06JTFUR100"))
    )
    (comp (ref "R142")
      (value "10k")
      (footprint "R0805")
      (description "Res Thick Film 0805 10K Ohm 5% 1/8W ±100ppm/°C Molded SMD Paper T/R")
      (fields
        (field (name "MANUFACTURER") "Yageo")
        (field (name "MANUFACTURER PART NUMBER") "RC0805JR-0710KL")
      )
      (libsource (lib "ER_SCHEMATIC_LIBRARY") (part "RC0805JR-0710KL"))
    )
    (comp (ref "R143")
      (value "1k")
      (footprint "R0603")
      (description "Rezystor: thick film; SMD; 0603; 1kΩ; 0,125W; ±5%; -55÷155°C")
      (fields (field (name "MANUFACTURER PART NUMBER") "WF06P102JTL"))
      (libsource (lib "ER_SCHEMATIC_LIBRARY") (part "WF06P102JTL"))
    )
    (comp (ref "TR100")
      (value "74043")
      (footprint "ERL28_MYRRA74043")
      (description "Transformator: impulsowy; 85VAC,265VAC; 3,3V; 5V; 7A; 7A; PCB; 60W")
      (libsource (lib "ER_SCHEMATIC_LIBRARY") (part "74043_MYRRA"))
    )
    (comp (ref "U100")
      (value "ICE2QS03G")
      (footprint "PG_DSO_8")
      (description "AC/DC Converters Quasi-Resonant PWM Controller")
      (fields (field (name "MANUFACTURER") "Infineon"))
      (libsource (lib "ER_SCHEMATIC_LIBRARY") (part "ICE2QS03G"))
    )
    (comp (ref "U101")
      (value "ATL432BQDBZR")
      (footprint "SOT23")
      (description "V-Ref Adjustable 2.5V to 36V 100mA Automotive 3-Pin SOT-23 T/R")
      (fields (field (name "MANUFACTURER") "Texas Instruments") (field (name "TOLERANCE") "0.5%"))
      (libsource (lib "ER_SCHEMATIC_LIBRARY") (part "ATL432BQDBZR"))
    )
    (comp (ref "U102")
      (value "TL432BQDBZR")
      (footprint "SOT23")
      (description "IC VREF SHUNT ADJ SOT23-3")
      (fields (field (name "MANUFACTURER") "Texas Instruments") (field (name "TOLERANCE") "0.5%"))
      (libsource (lib "ER_SCHEMATIC_LIBRARY") (part "TL432BQDBZR"))
    )
    (comp (ref "U103")
      (value "L7805C-V")
      (footprint "TO220AB")
      (description "L7805 Series 5 V 1.5 A Fixed Flange Mount Voltage Regulator - TO-220-3")
      (fields (field (name "MANUFACTURER") "STMicroelectronics") (field (name "TOLERANCE") "5%"))
      (libsource (lib "ER_SCHEMATIC_LIBRARY") (part "L7805C-V"))
    )
    (comp (ref "U104")
      (value "TPS92200D2DDCR")
      (footprint "SOT23_6")
      (fields (field (name "MANUFACTURER") "Texas Instruments"))
      (libsource (lib "ER_SCHEMATIC_LIBRARY") (part "TPS92200D2DDCR"))
    )
    (comp (ref "U105")
      (value "TLV9002IDDFR")
      (footprint "SOT23_8")
      (description "2-channel, 1-MHz, RRIO, 1.8-V to 5.5-V operational amplifier 8-SOT-23-THIN -40 to 125")
      (fields (field (name "MANUFACTURER") "Texas Instruments"))
      (libsource (lib "ER_SCHEMATIC_LIBRARY") (part "TLV9002IDDFR"))
    )
    (comp (ref "U106")
      (value "TLV7021DCKR")
      (footprint "SOT23_5")
      (description "Low power, small size comparator with open-drain output 5-SC70 -40 to 125")
      (fields (field (name "MANUFACTURER") "Texas Instruments"))
      (libsource (lib "ER_SCHEMATIC_LIBRARY") (part "TLV7021DCKR"))
    )
    (comp (ref "U107")
      (value "TL432BQDBZR")
      (footprint "SOT23")
      (description "IC VREF SHUNT ADJ SOT23-3")
      (fields (field (name "MANUFACTURER") "Texas Instruments") (field (name "TOLERANCE") "0.5%"))
      (libsource (lib "ER_SCHEMATIC_LIBRARY") (part "TL432BQDBZR"))
    )
    (comp (ref "VR100")
      (value "275VAC / 350VDC")
      (footprint "VAR_MOV_0_6X25")
      (description "Var MOV 275VAC/350VDC 400A 430V Thru-Hole Radial Bulk / VARISTOR 430V 400A DISC 5MM")
      (fields
        (field (name "MANUFACTURER") "TDK EPCOS")
        (field (name "MANUFACTURER PART NUMBER") "B72205S0271K101")
      )
      (libsource (lib "ER_SCHEMATIC_LIBRARY") (part "B72205S0271K101"))
    )
  )
  (nets
    (net (code "1") (name "+5V") (class "Default")
      (node (ref "C123") (pin "1") (pinfunction "1_1") (pintype "passive"))
      (node (ref "C124") (pin "1") (pinfunction "1_1") (pintype "passive"))
      (node (ref "C130") (pin "2") (pinfunction "2_2") (pintype "passive"))
      (node (ref "C131") (pin "2") (pinfunction "2_2") (pintype "passive"))
      (node (ref "R130") (pin "1") (pinfunction "1_1") (pintype "passive"))
      (node (ref "R136") (pin "1") (pinfunction "1_1") (pintype "passive"))
      (node (ref "U103") (pin "3") (pinfunction "OUT_3") (pintype "passive"))
      (node (ref "U105") (pin "8") (pinfunction "V+_8") (pintype "power_in"))
      (node (ref "U106") (pin "5") (pinfunction "5_5") (pintype "passive"))
    )
    (net (code "2") (name "+20V") (class "Default")
      (node (ref "C104") (pin "1") (pinfunction "1_1") (pintype "passive"))
      (node (ref "C105") (pin "1") (pinfunction "1_1") (pintype "passive"))
      (node (ref "C108") (pin "1") (pinfunction "1_1") (pintype "passive"))
      (node (ref "C121") (pin "1") (pinfunction "1_1") (pintype "passive"))
      (node (ref "C122") (pin "1") (pinfunction "1_1") (pintype "passive"))
      (node (ref "C125") (pin "1") (pinfunction "1_1") (pintype "passive"))
      (node (ref "C126") (pin "1") (pinfunction "1_1") (pintype "passive"))
      (node (ref "C127") (pin "1") (pinfunction "1_1") (pintype "passive"))
      (node (ref "L101") (pin "2") (pinfunction "2_2") (pintype "passive"))
      (node (ref "R104") (pin "2") (pinfunction "2_2") (pintype "passive"))
      (node (ref "U103") (pin "1") (pinfunction "IN_1") (pintype "passive"))
      (node (ref "U104") (pin "4") (pinfunction "VIN_4") (pintype "passive"))
    )
    (net (code "3") (name "/I_BAT") (class "Default")
      (node (ref "R134") (pin "2") (pinfunction "2_2") (pintype "passive"))
      (node (ref "U105") (pin "5") (pinfunction "IN2+_5") (pintype "tri_state"))
    )
    (net (code "4") (name "/VBAT_SENS") (class "Default")
      (node (ref "D105") (pin "1") (pinfunction "C_1") (pintype "passive"))
      (node (ref "R140") (pin "2") (pinfunction "2_2") (pintype "passive"))
      (node (ref "U104") (pin "1") (pinfunction "FB_1") (pintype "passive"))
      (node (ref "U105") (pin "2") (pinfunction "IN1-_2") (pintype "tri_state"))
    )
    (net (code "5") (name "/VREF") (class "Default")
      (node (ref "R136") (pin "2") (pinfunction "2_2") (pintype "passive"))
      (node (ref "R143") (pin "2") (pinfunction "2_2") (pintype "passive"))
      (node (ref "U106") (pin "4") (pinfunction "4_4") (pintype "passive"))
      (node (ref "U107") (pin "2") (pinfunction "2_2") (pintype "passive"))
    )
    (net (code "6") (name "/V_BAT_+") (class "Default")
      (node (ref "D104") (pin "1") (pinfunction "C_1") (pintype "passive"))
      (node (ref "PL103") (pin "1") (pinfunction "1_1") (pintype "passive"))
      (node (ref "R131") (pin "2") (pinfunction "2_2") (pintype "passive"))
    )
    (net (code "7") (name "/V_BAT_-") (class "Default")
      (node (ref "PL104") (pin "1") (pinfunction "1_1") (pintype "passive"))
      (node (ref "R135") (pin "2") (pinfunction "2_2") (pintype "passive"))
      (node (ref "R137") (pin "1") (pinfunction "1_1") (pintype "passive"))
    )
    (net (code "8") (name "/V_PRE") (class "Default")
      (node (ref "R133") (pin "1") (pinfunction "1_1") (pintype "passive"))
      (node (ref "R138") (pin "2") (pinfunction "2_2") (pintype "passive"))
      (node (ref "U106") (pin "3") (pinfunction "3_3") (pintype "passive"))
    )
    (net (code "9") (name "GND") (class "Default")
      (node (ref "CX100") (pin "2") (pinfunction "2_2") (pintype "passive"))
      (node (ref "CX102") (pin "1") (pinfunction "1_1") (pintype "passive"))
      (node (ref "PL101") (pin "1") (pinfunction "1_1") (pintype "passive"))
    )
    (net (code "10") (name "Net-(C102-Pad1)") (class "Default")
      (node (ref "C102") (pin "1") (pinfunction "1_1") (pintype "passive"))
      (node (ref "C103") (pin "1") (pinfunction "1_1") (pintype "passive"))
      (node (ref "C106") (pin "1") (pinfunction "1_1") (pintype "passive"))
      (node (ref "C107") (pin "1") (pinfunction "1_1") (pintype "passive"))
      (node (ref "C115") (pin "2") (pinfunction "2_2") (pintype "passive"))
      (node (ref "D100") (pin "2") (pinfunction "2_2") (pintype "passive"))
      (node (ref "L101") (pin "1") (pinfunction "1_1") (pintype "passive"))
      (node (ref "R120") (pin "2") (pinfunction "2_2") (pintype "passive"))
    )
    (net (code "11") (name "Net-(C110-Pad1)") (class "Default")
      (node (ref "C110") (pin "1") (pinfunction "1_1") (pintype "passive"))
      (node (ref "C111") (pin "1") (pinfunction "1_1") (pintype "passive"))
      (node (ref "R103") (pin "1") (pinfunction "1_1") (pintype "passive"))
      (node (ref "R107") (pin "2") (pinfunction "2_2") (pintype "passive"))
    )
    (net (code "12") (name "Net-(C115-Pad1)") (class "Default")
      (node (ref "C115") (pin "1") (pinfunction "1_1") (pintype "passive"))
      (node (ref "R120") (pin "1") (pinfunction "1_1") (pintype "passive"))
      (node (ref "R121") (pin "2") (pinfunction "2_2") (pintype "passive"))
    )
    (net (code "13") (name "Net-(C116-Pad1)") (class "Default")
      (node (ref "C116") (pin "1") (pinfunction "1_1") (pintype "passive"))
      (node (ref "R111") (pin "1") (pinfunction "1_1") (pintype "passive"))
      (node (ref "R123") (pin "2") (pinfunction "2_2") (pintype "passive"))
      (node (ref "R124") (pin "2") (pinfunction "2_2") (pintype "passive"))
      (node (ref "U101") (pin "1") (pinfunction "1_1") (pintype "passive"))
    )
    (net (code "14") (name "Net-(C117-Pad1)") (class "Default")
      (node (ref "C117") (pin "1") (pinfunction "1_1") (pintype "passive"))
      (node (ref "Q101") (pin "1") (pinfunction "1_1") (pintype "passive"))
      (node (ref "Q102") (pin "1") (pinfunction "1_1") (pintype "passive"))
      (node (ref "R122") (pin "1") (pinfunction "1_1") (pintype "passive"))
      (node (ref "R126") (pin "2") (pinfunction "2_2") (pintype "passive"))
    )
    (net (code "15") (name "Net-(C118-Pad1)") (class "Default")
      (node (ref "C118") (pin "1") (pinfunction "1_1") (pintype "passive"))
      (node (ref "C119") (pin "2") (pinfunction "2_2") (pintype "passive"))
      (node (ref "R119") (pin "1") (pinfunction "1_1") (pintype "passive"))
      (node (ref "R128") (pin "2") (pinfunction "2_2") (pintype "passive"))
      (node (ref "R129") (pin "2") (pinfunction "2_2") (pintype "passive"))
      (node (ref "U102") (pin "1") (pinfunction "1_1") (pintype "passive"))
    )
    (net (code "16") (name "Net-(C118-Pad2)") (class "Default")
      (node (ref "C118") (pin "2") (pinfunction "2_2") (pintype "passive"))
      (node (ref "R127") (pin "1") (pinfunction "1_1") (pintype "passive"))
    )
    (net (code "17") (name "Net-(C119-Pad1)") (class "Default")
      (node (ref "C119") (pin "1") (pinfunction "1_1") (pintype "passive"))
      (node (ref "OC100") (pin "2") (pinfunction "C_2") (pintype "passive"))
      (node (ref "R125") (pin "2") (pinfunction "2_2") (pintype "passive"))
      (node (ref "R127") (pin "2") (pinfunction "2_2") (pintype "passive"))
      (node (ref "U102") (pin "2") (pinfunction "2_2") (pintype "passive"))
    )
    (net (code "18") (name "Net-(CMC100-Pad1)") (class "Default")
      (node (ref "CMC100") (pin "1") (pinfunction "1_1") (pintype "passive"))
      (node (ref "CX101") (pin "1") (pinfunction "1_1") (pintype "passive"))
      (node (ref "F100") (pin "2") (pinfunction "2_2") (pintype "passive"))
      (node (ref "R100") (pin "2") (pinfunction "2_2") (pintype "passive"))
      (node (ref "VR100") (pin "1") (pinfunction "1_1") (pintype "passive"))
    )
    (net (code "19") (name "Net-(CMC100-Pad2)") (class "Default")
      (node (ref "CMC100") (pin "2") (pinfunction "2_2") (pintype "passive"))
      (node (ref "L100") (pin "1") (pinfunction "1_1") (pintype "passive"))
    )
    (net (code "20") (name "Net-(CMC100-Pad4)") (class "Default")
      (node (ref "CMC100") (pin "4") (pinfunction "4_4") (pintype "passive"))
      (node (ref "CX101") (pin "2") (pinfunction "2_2") (pintype "passive"))
      (node (ref "PL102") (pin "1") (pinfunction "1_1") (pintype "passive"))
      (node (ref "R101") (pin "1") (pinfunction "1_1") (pintype "passive"))
      (node (ref "VR100") (pin "2") (pinfunction "2_2") (pintype "passive"))
    )
    (net (code "21") (name "Net-(D100-Pad1)") (class "Default")
      (node (ref "D100") (pin "1") (pinfunction "1_1") (pintype "passive"))
      (node (ref "D100") (pin "3") (pinfunction "3_3") (pintype "passive"))
      (node (ref "TR100") (pin "18") (pinfunction "18_18") (pintype "passive"))
    )
    (net (code "22") (name "Net-(D101-A)") (class "Default")
      (node (ref "C113") (pin "1") (pinfunction "1_1") (pintype "passive"))
      (node (ref "D101") (pin "2") (pinfunction "A_2") (pintype "passive"))
      (node (ref "Q100") (pin "2") (pinfunction "2_2") (pintype "passive"))
      (node (ref "TR100") (pin "5") (pinfunction "5_5") (pintype "passive"))
    )
    (net (code "23") (name "Net-(D101-C)") (class "Default")
      (node (ref "C109") (pin "2") (pinfunction "2_2") (pintype "passive"))
      (node (ref "D101") (pin "1") (pinfunction "C_1") (pintype "passive"))
      (node (ref "R102") (pin "1") (pinfunction "1_1") (pintype "passive"))
    )
    (net (code "24") (name "Net-(D102-A)") (class "Default")
      (node (ref "D102") (pin "2") (pinfunction "A_2") (pintype "passive"))
      (node (ref "R106") (pin "2") (pinfunction "2_2") (pintype "passive"))
      (node (ref "TR100") (pin "8") (pinfunction "8_8") (pintype "passive"))
    )
    (net (code "25") (name "Net-(D102-C)") (class "Default")
      (node (ref "D102") (pin "1") (pinfunction "C_1") (pintype "passive"))
      (node (ref "R103") (pin "2") (pinfunction "2_2") (pintype "passive"))
    )
    (net (code "26") (name "Net-(D103-A)") (class "Default")
      (node (ref "D103") (pin "2") (pinfunction "A_2") (pintype "passive"))
      (node (ref "R108") (pin "1") (pinfunction "1_1") (pintype "passive"))
    )
    (net (code "27") (name "Net-(D103-C)") (class "Default")
      (node (ref "D103") (pin "1") (pinfunction "C_1") (pintype "passive"))
      (node (ref "R110") (pin "1") (pinfunction "1_1") (pintype "passive"))
      (node (ref "U100") (pin "4") (pinfunction "GATE_4") (pintype "output"))
    )
    (net (code "28") (name "Net-(D104-A)") (class "Default")
      (node (ref "C128") (pin "1") (pinfunction "1_1") (pintype "passive"))
      (node (ref "C129") (pin "1") (pinfunction "1_1") (pintype "passive"))
      (node (ref "D104") (pin "2") (pinfunction "A_2") (pintype "passive"))
      (node (ref "L102") (pin "2") (pinfunction "2_2") (pintype "passive"))
    )
    (net (code "29") (name "Net-(D105-A)") (class "Default")
      (node (ref "D105") (pin "2") (pinfunction "A_2") (pintype "passive"))
      (node (ref "U105") (pin "1") (pinfunction "OUT1_1") (pintype "passive"))
    )
    (net (code "30") (name "Net-(DBR100-+)") (class "Default")
      (node (ref "C100") (pin "1") (pinfunction "1_1") (pintype "passive"))
      (node (ref "C101") (pin "1") (pinfunction "1_1") (pintype "passive"))
      (node (ref "C109") (pin "1") (pinfunction "1_1") (pintype "passive"))
      (node (ref "DBR100") (pin "1") (pinfunction "+_1") (pintype "passive"))
      (node (ref "R102") (pin "2") (pinfunction "2_2") (pintype "passive"))
      (node (ref "R112") (pin "2") (pinfunction "2_2") (pintype "passive"))
      (node (ref "TR100") (pin "1") (pinfunction "1_1") (pintype "passive"))
      (node (ref "U100") (pin "5") (pinfunction "HV_5") (pintype "input"))
    )
    (net (code "31") (name "Net-(DBR100-1_~)") (class "Default")
      (node (ref "CX100") (pin "1") (pinfunction "1_1") (pintype "passive"))
      (node (ref "DBR100") (pin "2") (pinfunction "1_~_2") (pintype "passive"))
      (node (ref "L100") (pin "2") (pinfunction "2_2") (pintype "passive"))
    )
    (net (code "32") (name "Net-(DBR100-2_~)") (class "Default")
      (node (ref "CMC100") (pin "3") (pinfunction "3_3") (pintype "passive"))
      (node (ref "CX102") (pin "2") (pinfunction "2_2") (pintype "passive"))
      (node (ref "DBR100") (pin "3") (pinfunction "2_~_3") (pintype "passive"))
    )
    (net (code "33") (name "Net-(F100-Pad1)") (class "Default")
      (node (ref "F100") (pin "1") (pinfunction "1_1") (pintype "passive"))
      (node (ref "PL100") (pin "1") (pinfunction "1_1") (pintype "passive"))
    )
    (net (code "34") (name "Net-(OC100-A)") (class "Default")
      (node (ref "OC100") (pin "1") (pinfunction "A_1") (pintype "passive"))
      (node (ref "R121") (pin "1") (pinfunction "1_1") (pintype "passive"))
      (node (ref "R125") (pin "1") (pinfunction "1_1") (pintype "passive"))
    )
    (net (code "35") (name "Net-(Q100-Pad1)") (class "Default")
      (node (ref "Q100") (pin "1") (pinfunction "1_1") (pintype "passive"))
      (node (ref "R108") (pin "2") (pinfunction "2_2") (pintype "passive"))
      (node (ref "R110") (pin "2") (pinfunction "2_2") (pintype "passive"))
      (node (ref "R114") (pin "1") (pinfunction "1_1") (pintype "passive"))
    )
    (net (code "36") (name "Net-(Q102-Pad3)") (class "Default")
      (node (ref "Q102") (pin "3") (pinfunction "3_3") (pintype "passive"))
      (node (ref "R123") (pin "1") (pinfunction "1_1") (pintype "passive"))
    )
    (net (code "37") (name "Net-(R100-Pad1)") (class "Default")
      (node (ref "R100") (pin "1") (pinfunction "1_1") (pintype "passive"))
      (node (ref "R101") (pin "2") (pinfunction "2_2") (pintype "passive"))
    )
    (net (code "38") (name "Net-(R104-Pad1)") (class "Default")
      (node (ref "R104") (pin "1") (pinfunction "1_1") (pintype "passive"))
      (node (ref "R119") (pin "2") (pinfunction "2_2") (pintype "passive"))
    )
    (net (code "39") (name "Net-(R107-Pad1)") (class "Default")
      (node (ref "R107") (pin "1") (pinfunction "1_1") (pintype "passive"))
      (node (ref "R109") (pin "2") (pinfunction "2_2") (pintype "passive"))
    )
    (net (code "40") (name "Net-(R109-Pad1)") (class "Default")
      (node (ref "R109") (pin "1") (pinfunction "1_1") (pintype "passive"))
      (node (ref "R113") (pin "2") (pinfunction "2_2") (pintype "passive"))
    )
    (net (code "41") (name "Net-(R111-Pad2)") (class "Default")
      (node (ref "R111") (pin "2") (pinfunction "2_2") (pintype "passive"))
      (node (ref "R112") (pin "1") (pinfunction "1_1") (pintype "passive"))
    )
    (net (code "42") (name "Net-(R118-Pad1)") (class "Default")
      (node (ref "R118") (pin "1") (pinfunction "1_1") (pintype "passive"))
      (node (ref "R122") (pin "2") (pinfunction "2_2") (pintype "passive"))
      (node (ref "U101") (pin "2") (pinfunction "2_2") (pintype "passive"))
    )
    (net (code "43") (name "Net-(R131-Pad1)") (class "Default")
      (node (ref "R131") (pin "1") (pinfunction "1_1") (pintype "passive"))
      (node (ref "R133") (pin "2") (pinfunction "2_2") (pintype "passive"))
    )
    (net (code "44") (name "Net-(R134-Pad1)") (class "Default")
      (node (ref "R134") (pin "1") (pinfunction "1_1") (pintype "passive"))
      (node (ref "R135") (pin "1") (pinfunction "1_1") (pintype "passive"))
    )
    (net (code "45") (name "Net-(R137-Pad2)") (class "Default")
      (node (ref "R137") (pin "2") (pinfunction "2_2") (pintype "passive"))
      (node (ref "R141") (pin "1") (pinfunction "1_1") (pintype "passive"))
    )
    (net (code "46") (name "Net-(R138-Pad1)") (class "Default")
      (node (ref "R138") (pin "1") (pinfunction "1_1") (pintype "passive"))
      (node (ref "R140") (pin "1") (pinfunction "1_1") (pintype "passive"))
      (node (ref "R142") (pin "2") (pinfunction "2_2") (pintype "passive"))
    )
    (net (code "47") (name "Net-(R139-Pad2)") (class "Default")
      (node (ref "R139") (pin "2") (pinfunction "2_2") (pintype "passive"))
      (node (ref "U106") (pin "1") (pinfunction "1_1") (pintype "open_collector"))
    )
    (net (code "48") (name "Net-(R143-Pad1)") (class "Default")
      (node (ref "R143") (pin "1") (pinfunction "1_1") (pintype "passive"))
      (node (ref "U107") (pin "1") (pinfunction "1_1") (pintype "passive"))
    )
    (net (code "49") (name "Net-(U100-CS)") (class "Default")
      (node (ref "C113") (pin "2") (pinfunction "2_2") (pintype "passive"))
      (node (ref "Q100") (pin "3") (pinfunction "3_3") (pintype "passive"))
      (node (ref "R114") (pin "2") (pinfunction "2_2") (pintype "passive"))
      (node (ref "R116") (pin "2") (pinfunction "2_2") (pintype "passive"))
      (node (ref "R117") (pin "2") (pinfunction "2_2") (pintype "passive"))
      (node (ref "U100") (pin "3") (pinfunction "CS_3") (pintype "input"))
    )
    (net (code "50") (name "Net-(U100-FB)") (class "Default")
      (node (ref "OC100") (pin "4") (pinfunction "C_4") (pintype "passive"))
      (node (ref "Q101") (pin "3") (pinfunction "3_3") (pintype "passive"))
      (node (ref "U100") (pin "2") (pinfunction "FB_2") (pintype "input"))
    )
    (net (code "51") (name "Net-(U100-VCC)") (class "Default")
      (node (ref "C114") (pin "1") (pinfunction "1_1") (pintype "passive"))
      (node (ref "R113") (pin "1") (pinfunction "1_1") (pintype "passive"))
      (node (ref "R115") (pin "2") (pinfunction "2_2") (pintype "passive"))
      (node (ref "R118") (pin "2") (pinfunction "2_2") (pintype "passive"))
      (node (ref "U100") (pin "7") (pinfunction "VCC_7") (pintype "power_in"))
    )
    (net (code "52") (name "Net-(U100-ZC)") (class "Default")
      (node (ref "C112") (pin "2") (pinfunction "2_2") (pintype "passive"))
      (node (ref "R105") (pin "1") (pinfunction "1_1") (pintype "passive"))
      (node (ref "R106") (pin "1") (pinfunction "1_1") (pintype "passive"))
      (node (ref "U100") (pin "1") (pinfunction "ZC_1") (pintype "input"))
    )
    (net (code "53") (name "Net-(U104-BOOT)") (class "Default")
      (node (ref "C120") (pin "1") (pinfunction "1_1") (pintype "passive"))
      (node (ref "U104") (pin "6") (pinfunction "BOOT_6") (pintype "passive"))
    )
    (net (code "54") (name "Net-(U104-DIM)") (class "Default")
      (node (ref "R130") (pin "2") (pinfunction "2_2") (pintype "passive"))
      (node (ref "U104") (pin "2") (pinfunction "DIM_2") (pintype "passive"))
    )
    (net (code "55") (name "Net-(U104-SW)") (class "Default")
      (node (ref "C120") (pin "2") (pinfunction "2_2") (pintype "passive"))
      (node (ref "L102") (pin "1") (pinfunction "1_1") (pintype "passive"))
      (node (ref "U104") (pin "5") (pinfunction "SW_5") (pintype "passive"))
    )
    (net (code "56") (name "Net-(U105A-IN1+)") (class "Default")
      (node (ref "R132") (pin "2") (pinfunction "2_2") (pintype "passive"))
      (node (ref "U105") (pin "3") (pinfunction "IN1+_3") (pintype "tri_state"))
      (node (ref "U105") (pin "7") (pinfunction "OUT2_7") (pintype "passive"))
    )
    (net (code "57") (name "Net-(U105B-IN2-)") (class "Default")
      (node (ref "R132") (pin "1") (pinfunction "1_1") (pintype "passive"))
      (node (ref "R139") (pin "1") (pinfunction "1_1") (pintype "passive"))
      (node (ref "U105") (pin "6") (pinfunction "IN2-_6") (pintype "tri_state"))
    )
    (net (code "58") (name "PGND") (class "Default")
      (node (ref "C100") (pin "2") (pinfunction "2_2") (pintype "passive"))
      (node (ref "C101") (pin "2") (pinfunction "2_2") (pintype "passive"))
      (node (ref "C110") (pin "2") (pinfunction "2_2") (pintype "passive"))
      (node (ref "C111") (pin "2") (pinfunction "2_2") (pintype "passive"))
      (node (ref "C112") (pin "1") (pinfunction "1_1") (pintype "passive"))
      (node (ref "C114") (pin "2") (pinfunction "2_2") (pintype "passive"))
      (node (ref "C116") (pin "2") (pinfunction "2_2") (pintype "passive"))
      (node (ref "C117") (pin "2") (pinfunction "2_2") (pintype "passive"))
      (node (ref "CX103") (pin "1") (pinfunction "1_1") (pintype "passive"))
      (node (ref "DBR100") (pin "4") (pinfunction "-_4") (pintype "passive"))
      (node (ref "OC100") (pin "3") (pinfunction "E_3") (pintype "passive"))
      (node (ref "Q101") (pin "2") (pinfunction "2_2") (pintype "passive"))
      (node (ref "Q102") (pin "2") (pinfunction "2_2") (pintype "passive"))
      (node (ref "R105") (pin "2") (pinfunction "2_2") (pintype "passive"))
      (node (ref "R115") (pin "1") (pinfunction "1_1") (pintype "passive"))
      (node (ref "R116") (pin "1") (pinfunction "1_1") (pintype "passive"))
      (node (ref "R117") (pin "1") (pinfunction "1_1") (pintype "passive"))
      (node (ref "R124") (pin "1") (pinfunction "1_1") (pintype "passive"))
      (node (ref "R126") (pin "1") (pinfunction "1_1") (pintype "passive"))
      (node (ref "TR100") (pin "9") (pinfunction "9_9") (pintype "passive"))
      (node (ref "U100") (pin "8") (pinfunction "GND_8") (pintype "power_in"))
      (node (ref "U101") (pin "3") (pinfunction "3_3") (pintype "passive"))
    )
    (net (code "59") (name "SGND") (class "Default")
      (node (ref "C102") (pin "2") (pinfunction "2_2") (pintype "passive"))
      (node (ref "C103") (pin "2") (pinfunction "2_2") (pintype "passive"))
      (node (ref "C104") (pin "2") (pinfunction "2_2") (pintype "passive"))
      (node (ref "C105") (pin "2") (pinfunction "2_2") (pintype "passive"))
      (node (ref "C106") (pin "2") (pinfunction "2_2") (pintype "passive"))
      (node (ref "C107") (pin "2") (pinfunction "2_2") (pintype "passive"))
      (node (ref "C108") (pin "2") (pinfunction "2_2") (pintype "passive"))
      (node (ref "C121") (pin "2") (pinfunction "2_2") (pintype "passive"))
      (node (ref "C122") (pin "2") (pinfunction "2_2") (pintype "passive"))
      (node (ref "C123") (pin "2") (pinfunction "2_2") (pintype "passive"))
      (node (ref "C124") (pin "2") (pinfunction "2_2") (pintype "passive"))
      (node (ref "C125") (pin "2") (pinfunction "2_2") (pintype "passive"))
      (node (ref "C126") (pin "2") (pinfunction "2_2") (pintype "passive"))
      (node (ref "C127") (pin "2") (pinfunction "2_2") (pintype "passive"))
      (node (ref "C128") (pin "2") (pinfunction "2_2") (pintype "passive"))
      (node (ref "C129") (pin "2") (pinfunction "2_2") (pintype "passive"))
      (node (ref "C130") (pin "1") (pinfunction "1_1") (pintype "passive"))
      (node (ref "C131") (pin "1") (pinfunction "1_1") (pintype "passive"))
      (node (ref "CX103") (pin "2") (pinfunction "2_2") (pintype "passive"))
      (node (ref "R128") (pin "1") (pinfunction "1_1") (pintype "passive"))
      (node (ref "R129") (pin "1") (pinfunction "1_1") (pintype "passive"))
      (node (ref "R141") (pin "2") (pinfunction "2_2") (pintype "passive"))
      (node (ref "R142") (pin "1") (pinfunction "1_1") (pintype "passive"))
      (node (ref "TR100") (pin "12_13") (pinfunction "12_13_12_13") (pintype "passive"))
      (node (ref "U102") (pin "3") (pinfunction "3_3") (pintype "passive"))
      (node (ref "U103") (pin "2") (pinfunction "GND_2") (pintype "passive"))
      (node (ref "U104") (pin "3") (pinfunction "GND_3") (pintype "passive"))
      (node (ref "U105") (pin "4") (pinfunction "V-_4") (pintype "power_in"))
      (node (ref "U106") (pin "2") (pinfunction "2_2") (pintype "passive"))
      (node (ref "U107") (pin "3") (pinfunction "3_3") (pintype "passive"))
    )
    (net (code "60") (name "unconnected-(TR100-Pad3)") (class "Default")
      (node (ref "TR100") (pin "3") (pinfunction "3_3") (pintype "passive"))
    )
    (net (code "61") (name "unconnected-(TR100-Pad10)") (class "Default")
      (node (ref "TR100") (pin "10") (pinfunction "10_10") (pintype "passive+no_connect"))
    )
    (net (code "62") (name "unconnected-(TR100-Pad11)") (class "Default")
      (node (ref "TR100") (pin "11") (pinfunction "11_11") (pintype "passive+no_connect"))
    )
    (net (code "63") (name "unconnected-(TR100-Pad14_15)") (class "Default")
      (node (ref "TR100") (pin "14_15") (pinfunction "14_15_14_15") (pintype "passive+no_connect"))
    )
    (net (code "64") (name "unconnected-(TR100-Pad16)") (class "Default")
      (node (ref "TR100") (pin "16") (pinfunction "16_16") (pintype "passive+no_connect"))
    )
    (net (code "65") (name "unconnected-(TR100-Pad17)") (class "Default")
      (node (ref "TR100") (pin "17") (pinfunction "17_17") (pintype "passive+no_connect"))
    )
    (net (code "66") (name "unconnected-(U100-NC-Pad6)") (class "Default")
      (node (ref "U100") (pin "6") (pinfunction "NC_6") (pintype "passive+no_connect"))
    )
  )
)
